# Shutdown_Converter.net
KiCad netlist of a schematic drawn in Altium Designer
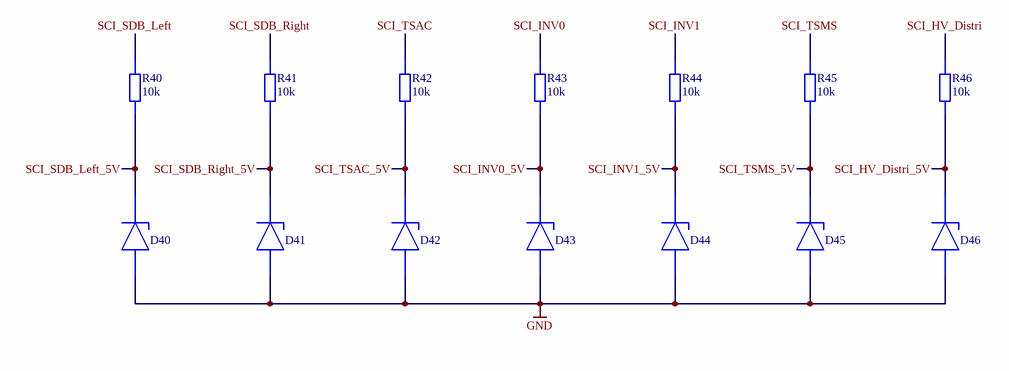
[diagram p0: Shutdown_Converter.SchDoc]

(export (version "E")
  (design (tool "Eeschema 10.0.6"))
  (components
    (comp (ref "D40")
      (value "MM3Z4V7T1G")
      (footprint "SOD-323-2")
      (description "onsemi MM3Z4V7T1G\r\nZ-Diode, 4,7V")
      (libsource (lib "libNico") (part "MM3Z4V7T1G"))
    )
    (comp (ref "D41")
      (value "MM3Z4V7T1G")
      (footprint "SOD-323-2")
      (description "onsemi MM3Z4V7T1G\r\nZ-Diode, 4,7V")
      (libsource (lib "libNico") (part "MM3Z4V7T1G"))
    )
    (comp (ref "D42")
      (value "MM3Z4V7T1G")
      (footprint "SOD-323-2")
      (description "onsemi MM3Z4V7T1G\r\nZ-Diode, 4,7V")
      (libsource (lib "libNico") (part "MM3Z4V7T1G"))
    )
    (comp (ref "D43")
      (value "MM3Z4V7T1G")
      (footprint "SOD-323-2")
      (description "onsemi MM3Z4V7T1G\r\nZ-Diode, 4,7V")
      (libsource (lib "libNico") (part "MM3Z4V7T1G"))
    )
    (comp (ref "D44")
      (value "MM3Z4V7T1G")
      (footprint "SOD-323-2")
      (description "onsemi MM3Z4V7T1G\r\nZ-Diode, 4,7V")
      (libsource (lib "libNico") (part "MM3Z4V7T1G"))
    )
    (comp (ref "D45")
      (value "MM3Z4V7T1G")
      (footprint "SOD-323-2")
      (description "onsemi MM3Z4V7T1G\r\nZ-Diode, 4,7V")
      (libsource (lib "libNico") (part "MM3Z4V7T1G"))
    )
    (comp (ref "D46")
      (value "MM3Z4V7T1G")
      (footprint "SOD-323-2")
      (description "onsemi MM3Z4V7T1G\r\nZ-Diode, 4,7V")
      (libsource (lib "libNico") (part "MM3Z4V7T1G"))
    )
    (comp (ref "R40")
      (value "10k")
      (footprint "STACKPOLE CSR0603")
      (description "Resistor with multiple footprints")
      (fields (field (name "Comment") "SMD Resistor"))
      (libsource (lib "Standardbauteile") (part "SMD Resistor"))
    )
    (comp (ref "R41")
      (value "10k")
      (footprint "STACKPOLE CSR0603")
      (description "Resistor with multiple footprints")
      (fields (field (name "Comment") "SMD Resistor"))
      (libsource (lib "Standardbauteile") (part "SMD Resistor"))
    )
    (comp (ref "R42")
      (value "10k")
      (footprint "STACKPOLE CSR0603")
      (description "Resistor with multiple footprints")
      (fields (field (name "Comment") "SMD Resistor"))
      (libsource (lib "Standardbauteile") (part "SMD Resistor"))
    )
    (comp (ref "R43")
      (value "10k")
      (footprint "STACKPOLE CSR0603")
      (description "Resistor with multiple footprints")
      (fields (field (name "Comment") "SMD Resistor"))
      (libsource (lib "Standardbauteile") (part "SMD Resistor"))
    )
    (comp (ref "R44")
      (value "10k")
      (footprint "STACKPOLE CSR0603")
      (description "Resistor with multiple footprints")
      (fields (field (name "Comment") "SMD Resistor"))
      (libsource (lib "Standardbauteile") (part "SMD Resistor"))
    )
    (comp (ref "R45")
      (value "10k")
      (footprint "STACKPOLE CSR0603")
      (description "Resistor with multiple footprints")
      (fields (field (name "Comment") "SMD Resistor"))
      (libsource (lib "Standardbauteile") (part "SMD Resistor"))
    )
    (comp (ref "R46")
      (value "10k")
      (footprint "STACKPOLE CSR0603")
      (description "Resistor with multiple footprints")
      (fields (field (name "Comment") "SMD Resistor"))
      (libsource (lib "Standardbauteile") (part "SMD Resistor"))
    )
  )
  (nets
    (net (code "1") (name "/SCI_HV_Distri") (class "Default")
      (node (ref "R46") (pin "2") (pinfunction "2_2") (pintype "passive"))
    )
    (net (code "2") (name "/SCI_HV_Distri_5V") (class "Default")
      (node (ref "D46") (pin "1C") (pinfunction "C_1C") (pintype "passive"))
      (node (ref "R46") (pin "1") (pinfunction "1_1") (pintype "passive"))
    )
    (net (code "3") (name "/SCI_INV0") (class "Default")
      (node (ref "R43") (pin "2") (pinfunction "2_2") (pintype "passive"))
    )
    (net (code "4") (name "/SCI_INV0_5V") (class "Default")
      (node (ref "D43") (pin "1C") (pinfunction "C_1C") (pintype "passive"))
      (node (ref "R43") (pin "1") (pinfunction "1_1") (pintype "passive"))
    )
    (net (code "5") (name "/SCI_INV1") (class "Default")
      (node (ref "R44") (pin "2") (pinfunction "2_2") (pintype "passive"))
    )
    (net (code "6") (name "/SCI_INV1_5V") (class "Default")
      (node (ref "D44") (pin "1C") (pinfunction "C_1C") (pintype "passive"))
      (node (ref "R44") (pin "1") (pinfunction "1_1") (pintype "passive"))
    )
    (net (code "7") (name "/SCI_SDB_Left") (class "Default")
      (node (ref "R40") (pin "2") (pinfunction "2_2") (pintype "passive"))
    )
    (net (code "8") (name "/SCI_SDB_Left_5V") (class "Default")
      (node (ref "D40") (pin "1C") (pinfunction "C_1C") (pintype "passive"))
      (node (ref "R40") (pin "1") (pinfunction "1_1") (pintype "passive"))
    )
    (net (code "9") (name "/SCI_SDB_Right") (class "Default")
      (node (ref "R41") (pin "2") (pinfunction "2_2") (pintype "passive"))
    )
    (net (code "10") (name "/SCI_SDB_Right_5V") (class "Default")
      (node (ref "D41") (pin "1C") (pinfunction "C_1C") (pintype "passive"))
      (node (ref "R41") (pin "1") (pinfunction "1_1") (pintype "passive"))
    )
    (net (code "11") (name "/SCI_TSAC") (class "Default")
      (node (ref "R42") (pin "2") (pinfunction "2_2") (pintype "passive"))
    )
    (net (code "12") (name "/SCI_TSAC_5V") (class "Default")
      (node (ref "D42") (pin "1C") (pinfunction "C_1C") (pintype "passive"))
      (node (ref "R42") (pin "1") (pinfunction "1_1") (pintype "passive"))
    )
    (net (code "13") (name "/SCI_TSMS") (class "Default")
      (node (ref "R45") (pin "2") (pinfunction "2_2") (pintype "passive"))
    )
    (net (code "14") (name "/SCI_TSMS_5V") (class "Default")
      (node (ref "D45") (pin "1C") (pinfunction "C_1C") (pintype "passive"))
      (node (ref "R45") (pin "1") (pinfunction "1_1") (pintype "passive"))
    )
    (net (code "15") (name "GND") (class "Default")
      (node (ref "D40") (pin "2A") (pinfunction "A_2A") (pintype "passive"))
      (node (ref "D41") (pin "2A") (pinfunction "A_2A") (pintype "passive"))
      (node (ref "D42") (pin "2A") (pinfunction "A_2A") (pintype "passive"))
      (node (ref "D43") (pin "2A") (pinfunction "A_2A") (pintype "passive"))
      (node (ref "D44") (pin "2A") (pinfunction "A_2A") (pintype "passive"))
      (node (ref "D45") (pin "2A") (pinfunction "A_2A") (pintype "passive"))
      (node (ref "D46") (pin "2A") (pinfunction "A_2A") (pintype "passive"))
    )
  )
)
